# accelerometer.net
KiCad netlist of a schematic drawn in Altium Designer
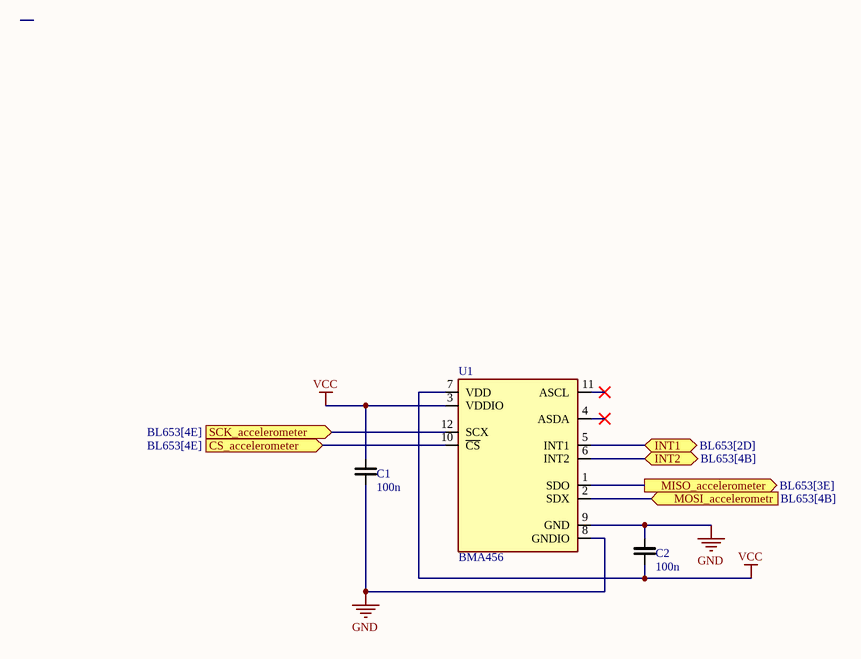
[diagram p0: accelerometer.SchDoc]

(export (version "E")
  (design (tool "Eeschema 10.0.6"))
  (components
    (comp (ref "C1")
      (value "100n")
      (footprint "0402_CAP_REFLOW")
      (description "Ceramic capacitor")
      (libsource (lib "Schlib1") (part "CAP_100n"))
    )
    (comp (ref "C2")
      (value "100n")
      (footprint "0402_CAP_REFLOW")
      (description "Ceramic capacitor")
      (libsource (lib "Schlib1") (part "CAP_100n"))
    )
    (comp (ref "U1")
      (value "BMA456")
      (footprint "FP-BMA456-MFG")
      (description "ACCEL 2-16G I2C/SPI 12LGA")
      (fields
        (field (name "MANUFACTURER") "Bosch Sensortec")
        (field (name "OCTOPART") "https://octopart.com/bma456-bosch+sensortec-99488369")
      )
      (libsource (lib "Schlib1") (part "CMP-191065-000002-1"))
    )
  )
  (nets
    (net (code "1") (name "/CS_accelerometer") (class "Default")
      (node (ref "U1") (pin "10") (pinfunction "~{CS}_10") (pintype "passive"))
    )
    (net (code "2") (name "/INT1") (class "Default")
      (node (ref "U1") (pin "5") (pinfunction "INT1_5") (pintype "passive"))
    )
    (net (code "3") (name "/INT2") (class "Default")
      (node (ref "U1") (pin "6") (pinfunction "INT2_6") (pintype "passive"))
    )
    (net (code "4") (name "/MISO_accelerometer") (class "Default")
      (node (ref "U1") (pin "1") (pinfunction "SDO_1") (pintype "passive"))
    )
    (net (code "5") (name "/MOSI_accelerometr") (class "Default")
      (node (ref "U1") (pin "2") (pinfunction "SDX_2") (pintype "passive"))
    )
    (net (code "6") (name "/SCK_accelerometer") (class "Default")
      (node (ref "U1") (pin "12") (pinfunction "SCX_12") (pintype "passive"))
    )
    (net (code "7") (name "GND") (class "Default")
      (node (ref "C1") (pin "1") (pinfunction "1_1") (pintype "passive"))
      (node (ref "C2") (pin "2") (pinfunction "2_2") (pintype "passive"))
      (node (ref "U1") (pin "8") (pinfunction "GNDIO_8") (pintype "passive"))
      (node (ref "U1") (pin "9") (pinfunction "GND_9") (pintype "passive"))
    )
    (net (code "8") (name "VCC") (class "Default")
      (node (ref "C1") (pin "2") (pinfunction "2_2") (pintype "passive"))
      (node (ref "C2") (pin "1") (pinfunction "1_1") (pintype "passive"))
      (node (ref "U1") (pin "3") (pinfunction "VDDIO_3") (pintype "passive"))
      (node (ref "U1") (pin "7") (pinfunction "VDD_7") (pintype "passive"))
    )
    (net (code "9") (name "unconnected-(U1-ASCL-Pad11)") (class "Default")
      (node (ref "U1") (pin "11") (pinfunction "ASCL_11") (pintype "passive"))
    )
    (net (code "10") (name "unconnected-(U1-ASDA-Pad4)") (class "Default")
      (node (ref "U1") (pin "4") (pinfunction "ASDA_4") (pintype "passive"))
    )
  )
)
